# Integrador.net
KiCad netlist of a schematic drawn in EAGLE
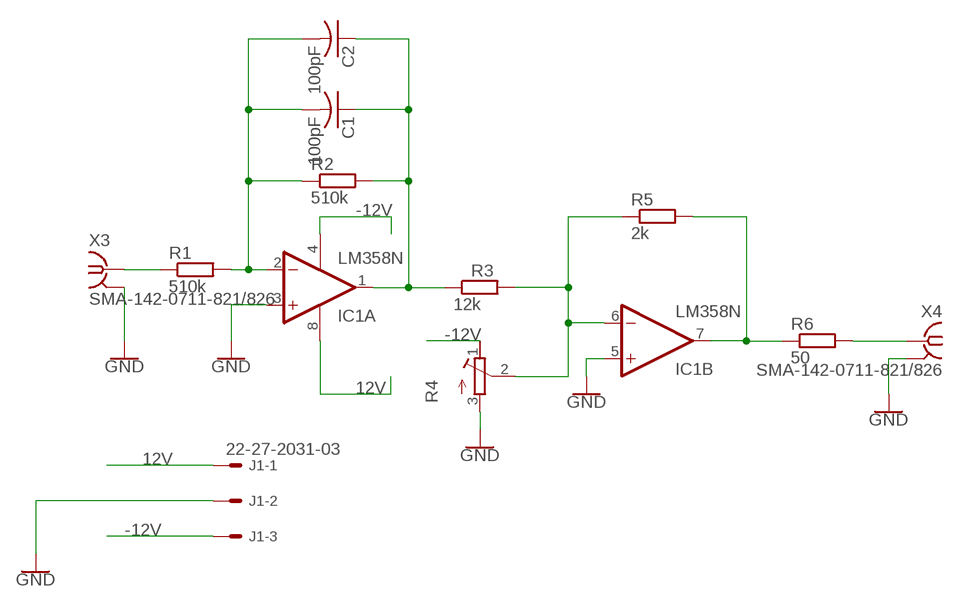
[diagram p0: schematic, sheet 1]

(export (version "E")
  (design (tool "Eeschema 10.0.6"))
  (components
    (comp (ref "C1")
      (value "100pF")
      (footprint "eagle-import:C025-030X050")
      (libsource (lib "eagle-import") (part "C-US025-030X050"))
    )
    (comp (ref "C2")
      (value "100pF")
      (footprint "eagle-import:C025-030X050")
      (libsource (lib "eagle-import") (part "C-US025-030X050"))
    )
    (comp (ref "IC1")
      (value "LM358N")
      (footprint "eagle-import:DIL08")
      (libsource (lib "eagle-import") (part "LM358N"))
    )
    (comp (ref "J1")
      (value "22-27-2031-03")
      (footprint "eagle-import:6410-03")
      (fields (field (name "MF") "MOLEX"))
      (libsource (lib "eagle-import") (part "22-?-0327-2031"))
    )
    (comp (ref "R1")
      (value "510k")
      (footprint "eagle-import:0207_10")
      (libsource (lib "eagle-import") (part "R-EU_0207/10"))
    )
    (comp (ref "R2")
      (value "510k")
      (footprint "eagle-import:0207_10")
      (libsource (lib "eagle-import") (part "R-EU_0207/10"))
    )
    (comp (ref "R3")
      (value "12k")
      (footprint "eagle-import:0207_10")
      (libsource (lib "eagle-import") (part "R-EU_0207/10"))
    )
    (comp (ref "R4")
      (value "R-TRIMM3006P")
      (footprint "eagle-import:RTRIM3006P")
      (libsource (lib "eagle-import") (part "R-TRIMM3006P"))
    )
    (comp (ref "R5")
      (value "2k")
      (footprint "eagle-import:0207_10")
      (libsource (lib "eagle-import") (part "R-EU_0207/10"))
    )
    (comp (ref "R6")
      (value "50")
      (footprint "eagle-import:0207_10")
      (libsource (lib "eagle-import") (part "R-EU_0207/10"))
    )
    (comp (ref "X3")
      (value "SMA-142-0711-821/826")
      (footprint "eagle-import:J502-ND-142-0711-821_826")
      (fields (field (name "MF") "JOHNSON COMPONENTS") (field (name "MPN") "142-0711-821"))
      (libsource (lib "eagle-import") (part "SMA-142-0711-821/826"))
    )
    (comp (ref "X4")
      (value "SMA-142-0711-821/826")
      (footprint "eagle-import:J502-ND-142-0711-821_826")
      (fields (field (name "MF") "JOHNSON COMPONENTS") (field (name "MPN") "142-0711-821"))
      (libsource (lib "eagle-import") (part "SMA-142-0711-821/826"))
    )
  )
  (nets
    (net (code "1") (name "/-12V") (class "Default")
      (node (ref "IC1") (pin "4") (pinfunction "V-_4") (pintype "power_in"))
      (node (ref "J1") (pin "3") (pinfunction "S_3") (pintype "passive"))
      (node (ref "R4") (pin "1") (pinfunction "E_1") (pintype "passive"))
    )
    (net (code "2") (name "/12V") (class "Default")
      (node (ref "IC1") (pin "8") (pinfunction "V+_8") (pintype "power_in"))
      (node (ref "J1") (pin "1") (pinfunction "S_1") (pintype "passive"))
    )
    (net (code "3") (name "GND") (class "Default")
      (node (ref "IC1") (pin "3") (pinfunction "+IN_3") (pintype "input"))
      (node (ref "IC1") (pin "5") (pinfunction "+IN_5") (pintype "input"))
      (node (ref "J1") (pin "2") (pinfunction "S_2") (pintype "passive"))
      (node (ref "R4") (pin "3") (pinfunction "A_3") (pintype "passive"))
      (node (ref "X3") (pin "G@1") (pinfunction "2_G@1") (pintype "passive"))
      (node (ref "X3") (pin "G@2") (pinfunction "2_G@2") (pintype "passive"))
      (node (ref "X3") (pin "G@3") (pinfunction "2_G@3") (pintype "passive"))
      (node (ref "X3") (pin "G@4") (pinfunction "2_G@4") (pintype "passive"))
      (node (ref "X4") (pin "G@1") (pinfunction "2_G@1") (pintype "passive"))
      (node (ref "X4") (pin "G@2") (pinfunction "2_G@2") (pintype "passive"))
      (node (ref "X4") (pin "G@3") (pinfunction "2_G@3") (pintype "passive"))
      (node (ref "X4") (pin "G@4") (pinfunction "2_G@4") (pintype "passive"))
    )
    (net (code "4") (name "Net-(IC1A--IN)") (class "Default")
      (node (ref "C1") (pin "2") (pinfunction "2_2") (pintype "passive"))
      (node (ref "C2") (pin "2") (pinfunction "2_2") (pintype "passive"))
      (node (ref "IC1") (pin "2") (pinfunction "-IN_2") (pintype "input"))
      (node (ref "R1") (pin "2") (pinfunction "2_2") (pintype "passive"))
      (node (ref "R2") (pin "1") (pinfunction "1_1") (pintype "passive"))
    )
    (net (code "5") (name "Net-(IC1A-OUT)") (class "Default")
      (node (ref "C1") (pin "1") (pinfunction "1_1") (pintype "passive"))
      (node (ref "C2") (pin "1") (pinfunction "1_1") (pintype "passive"))
      (node (ref "IC1") (pin "1") (pinfunction "OUT_1") (pintype "output"))
      (node (ref "R2") (pin "2") (pinfunction "2_2") (pintype "passive"))
      (node (ref "R3") (pin "1") (pinfunction "1_1") (pintype "passive"))
    )
    (net (code "6") (name "Net-(IC1B--IN)") (class "Default")
      (node (ref "IC1") (pin "6") (pinfunction "-IN_6") (pintype "input"))
      (node (ref "R3") (pin "2") (pinfunction "2_2") (pintype "passive"))
      (node (ref "R4") (pin "2") (pinfunction "S_2") (pintype "passive"))
      (node (ref "R5") (pin "1") (pinfunction "1_1") (pintype "passive"))
    )
    (net (code "7") (name "Net-(IC1B-OUT)") (class "Default")
      (node (ref "IC1") (pin "7") (pinfunction "OUT_7") (pintype "output"))
      (node (ref "R5") (pin "2") (pinfunction "2_2") (pintype "passive"))
      (node (ref "R6") (pin "1") (pinfunction "1_1") (pintype "passive"))
    )
    (net (code "8") (name "Net-(R1-Pad1)") (class "Default")
      (node (ref "R1") (pin "1") (pinfunction "1_1") (pintype "passive"))
      (node (ref "X3") (pin "1") (pinfunction "1_1") (pintype "passive"))
    )
    (net (code "9") (name "Net-(R6-Pad2)") (class "Default")
      (node (ref "R6") (pin "2") (pinfunction "2_2") (pintype "passive"))
      (node (ref "X4") (pin "1") (pinfunction "1_1") (pintype "passive"))
    )
  )
)
